# MCT-1601.net
KiCad netlist of a schematic drawn in EAGLE
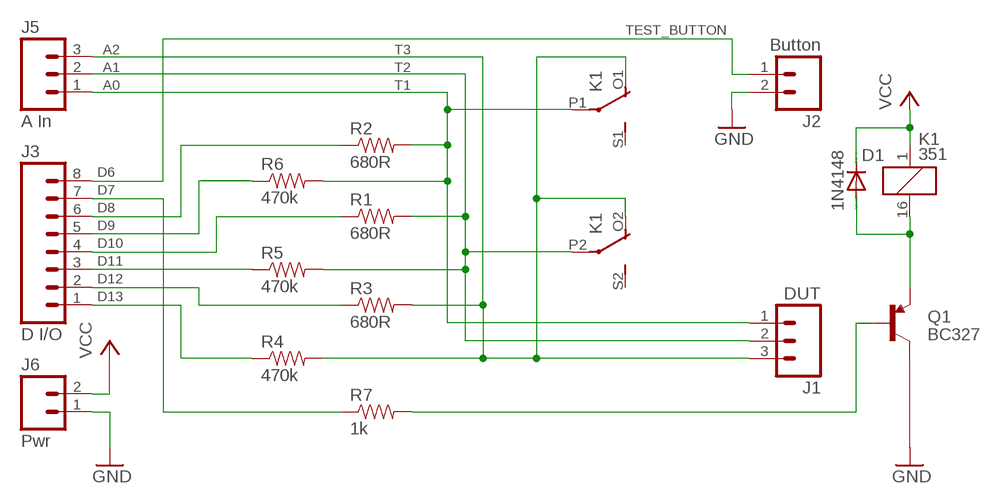
[diagram p0: schematic, sheet 1]

(export (version "E")
  (design (tool "Eeschema 10.0.6"))
  (components
    (comp (ref "D1")
      (value "1N4148")
      (footprint "eagle-import:D-2.5")
      (libsource (lib "eagle-import") (part "DIODE-D-2.5"))
    )
    (comp (ref "J1")
      (value "DUT")
      (footprint "eagle-import:1X03")
      (libsource (lib "eagle-import") (part "M03PTH"))
    )
    (comp (ref "J2")
      (value "Button")
      (footprint "eagle-import:1X02")
      (libsource (lib "eagle-import") (part "M02PTH"))
    )
    (comp (ref "J3")
      (value "D I/O")
      (footprint "eagle-import:1X08_ROUND")
      (libsource (lib "eagle-import") (part "M08"))
    )
    (comp (ref "J5")
      (value "A In")
      (footprint "eagle-import:1X03")
      (libsource (lib "eagle-import") (part "M03PTH"))
    )
    (comp (ref "J6")
      (value "Pwr")
      (footprint "eagle-import:1X02")
      (libsource (lib "eagle-import") (part "M02PTH"))
    )
    (comp (ref "K1")
      (value "351")
      (footprint "eagle-import:351")
      (libsource (lib "eagle-import") (part "351"))
    )
    (comp (ref "Q1")
      (value "BC327")
      (footprint "eagle-import:TO-92")
      (libsource (lib "eagle-import") (part "SS-PNP-BC327"))
    )
    (comp (ref "R1")
      (value "680R")
      (footprint "eagle-import:AXIAL-0.1")
      (libsource (lib "eagle-import") (part "1KOHM-1/4W-1%(PTH)VERT"))
    )
    (comp (ref "R2")
      (value "680R")
      (footprint "eagle-import:AXIAL-0.1")
      (libsource (lib "eagle-import") (part "1KOHM-1/4W-1%(PTH)VERT"))
    )
    (comp (ref "R3")
      (value "680R")
      (footprint "eagle-import:AXIAL-0.1")
      (libsource (lib "eagle-import") (part "1KOHM-1/4W-1%(PTH)VERT"))
    )
    (comp (ref "R4")
      (value "470k")
      (footprint "eagle-import:AXIAL-0.1")
      (libsource (lib "eagle-import") (part "1KOHM-1/4W-1%(PTH)VERT"))
    )
    (comp (ref "R5")
      (value "470k")
      (footprint "eagle-import:AXIAL-0.1")
      (libsource (lib "eagle-import") (part "1KOHM-1/4W-1%(PTH)VERT"))
    )
    (comp (ref "R6")
      (value "470k")
      (footprint "eagle-import:AXIAL-0.1")
      (libsource (lib "eagle-import") (part "1KOHM-1/4W-1%(PTH)VERT"))
    )
    (comp (ref "R7")
      (value "1k")
      (footprint "eagle-import:AXIAL-0.1")
      (libsource (lib "eagle-import") (part "1KOHM-1/4W-1%(PTH)VERT"))
    )
  )
  (nets
    (net (code "1") (name "/D7") (class "Default")
      (node (ref "J3") (pin "7") (pinfunction "7_7") (pintype "passive"))
      (node (ref "R7") (pin "P$1") (pinfunction "1_P$1") (pintype "passive"))
    )
    (net (code "2") (name "/D8") (class "Default")
      (node (ref "J3") (pin "6") (pinfunction "6_6") (pintype "passive"))
      (node (ref "R2") (pin "P$1") (pinfunction "1_P$1") (pintype "passive"))
    )
    (net (code "3") (name "/D9") (class "Default")
      (node (ref "J3") (pin "5") (pinfunction "5_5") (pintype "passive"))
      (node (ref "R6") (pin "P$1") (pinfunction "1_P$1") (pintype "passive"))
    )
    (net (code "4") (name "/D10") (class "Default")
      (node (ref "J3") (pin "4") (pinfunction "4_4") (pintype "passive"))
      (node (ref "R1") (pin "P$1") (pinfunction "1_P$1") (pintype "passive"))
    )
    (net (code "5") (name "/D11") (class "Default")
      (node (ref "J3") (pin "3") (pinfunction "3_3") (pintype "passive"))
      (node (ref "R5") (pin "P$1") (pinfunction "1_P$1") (pintype "passive"))
    )
    (net (code "6") (name "/D12") (class "Default")
      (node (ref "J3") (pin "2") (pinfunction "2_2") (pintype "passive"))
      (node (ref "R3") (pin "P$1") (pinfunction "1_P$1") (pintype "passive"))
    )
    (net (code "7") (name "/D13") (class "Default")
      (node (ref "J3") (pin "1") (pinfunction "1_1") (pintype "passive"))
      (node (ref "R4") (pin "P$1") (pinfunction "1_P$1") (pintype "passive"))
    )
    (net (code "8") (name "/T1") (class "Default")
      (node (ref "J1") (pin "1") (pinfunction "1_1") (pintype "passive"))
      (node (ref "J5") (pin "1") (pinfunction "1_1") (pintype "passive"))
      (node (ref "K1") (pin "P1") (pinfunction "P_P1") (pintype "passive"))
      (node (ref "R2") (pin "P$2") (pinfunction "2_P$2") (pintype "passive"))
      (node (ref "R6") (pin "P$2") (pinfunction "2_P$2") (pintype "passive"))
    )
    (net (code "9") (name "/T2") (class "Default")
      (node (ref "J1") (pin "2") (pinfunction "2_2") (pintype "passive"))
      (node (ref "J5") (pin "2") (pinfunction "2_2") (pintype "passive"))
      (node (ref "K1") (pin "P2") (pinfunction "P_P2") (pintype "passive"))
      (node (ref "R1") (pin "P$2") (pinfunction "2_P$2") (pintype "passive"))
      (node (ref "R5") (pin "P$2") (pinfunction "2_P$2") (pintype "passive"))
    )
    (net (code "10") (name "/T3") (class "Default")
      (node (ref "J1") (pin "3") (pinfunction "3_3") (pintype "passive"))
      (node (ref "J5") (pin "3") (pinfunction "3_3") (pintype "passive"))
      (node (ref "K1") (pin "O1") (pinfunction "O_O1") (pintype "passive"))
      (node (ref "K1") (pin "O2") (pinfunction "O_O2") (pintype "passive"))
      (node (ref "R3") (pin "P$2") (pinfunction "2_P$2") (pintype "passive"))
      (node (ref "R4") (pin "P$2") (pinfunction "2_P$2") (pintype "passive"))
    )
    (net (code "11") (name "/TEST_BUTTON") (class "Default")
      (node (ref "J2") (pin "1") (pinfunction "1_1") (pintype "passive"))
      (node (ref "J3") (pin "8") (pinfunction "8_8") (pintype "passive"))
    )
    (net (code "12") (name "GND") (class "Default")
      (node (ref "J2") (pin "2") (pinfunction "2_2") (pintype "passive"))
      (node (ref "J6") (pin "1") (pinfunction "1_1") (pintype "passive"))
      (node (ref "Q1") (pin "3") (pinfunction "C_3") (pintype "passive"))
    )
    (net (code "13") (name "Net-(K1A-2)") (class "Default")
      (node (ref "D1") (pin "A") (pinfunction "A_A") (pintype "passive"))
      (node (ref "K1") (pin "16") (pinfunction "2_16") (pintype "passive"))
      (node (ref "Q1") (pin "1") (pinfunction "E_1") (pintype "passive"))
    )
    (net (code "14") (name "Net-(Q1-B)") (class "Default")
      (node (ref "Q1") (pin "2") (pinfunction "B_2") (pintype "passive"))
      (node (ref "R7") (pin "P$2") (pinfunction "2_P$2") (pintype "passive"))
    )
    (net (code "15") (name "VCC") (class "Default")
      (node (ref "D1") (pin "C") (pinfunction "C_C") (pintype "passive"))
      (node (ref "J6") (pin "2") (pinfunction "2_2") (pintype "passive"))
      (node (ref "K1") (pin "1") (pinfunction "1_1") (pintype "passive"))
    )
    (net (code "16") (name "unconnected-(K1B-S-PadS1)") (class "Default")
      (node (ref "K1") (pin "S1") (pinfunction "S_S1") (pintype "passive"))
    )
    (net (code "17") (name "unconnected-(K1C-S-PadS2)") (class "Default")
      (node (ref "K1") (pin "S2") (pinfunction "S_S2") (pintype "passive"))
    )
  )
)
